# Modules_And_Sensors.net
KiCad netlist of a schematic drawn in Altium Designer
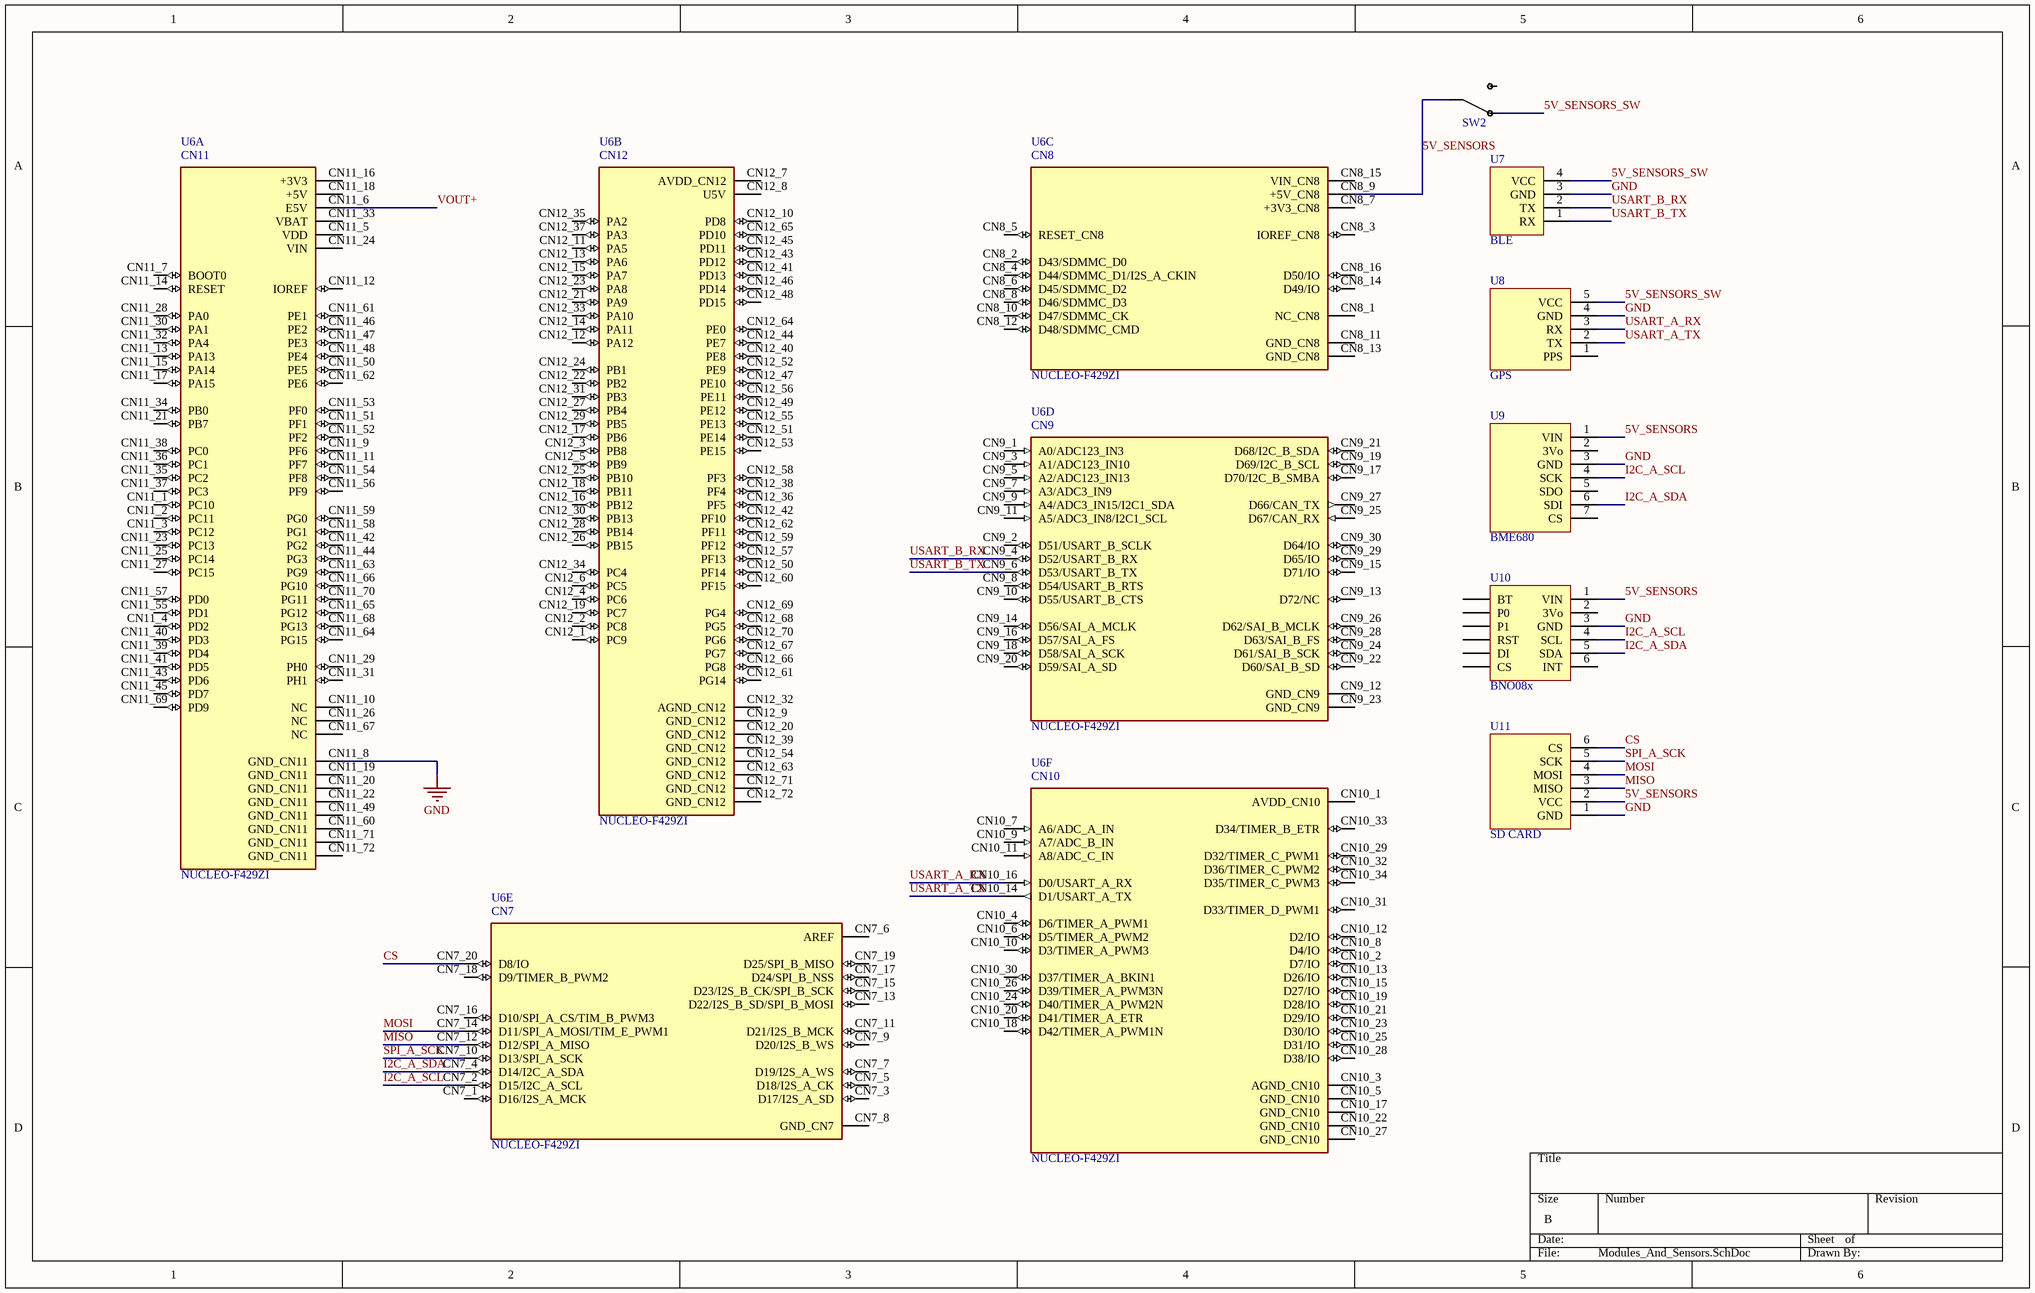
[diagram p0: Modules_And_Sensors.SchDoc]

(export (version "E")
  (design (tool "Eeschema 10.0.6"))
  (components
    (comp (ref "SW2") (value "SW") (footprint "SWITCH") (libsource (lib "Power_Schlib1") (part "Switch")))
    (comp (ref "U6")
      (value "NUCLEO-F429ZI")
      (footprint "MODULE_NUCLEO-F429ZI")
      (fields (field (name "MF") "STMicroelectronics"))
      (libsource (lib "NUCLEO-F429ZI") (part "NUCLEO-F429ZI"))
    )
    (comp (ref "U7") (value "BLE") (footprint "BLE") (libsource (lib "Power_Schlib1") (part "BLE")))
    (comp (ref "U8") (value "GPS") (footprint "GPS") (libsource (lib "Power_Schlib1") (part "GPS")))
    (comp (ref "U9") (value "BME680") (footprint "BME680") (libsource (lib "Power_Schlib1") (part "BME680")))
    (comp (ref "U10") (value "BNO08x") (footprint "BNO08x") (libsource (lib "Power_Schlib1") (part "BNO08x")))
    (comp (ref "U11")
      (value "SD CARD")
      (footprint "SD CARD")
      (libsource (lib "Power_Schlib1") (part "SD Card"))
    )
  )
  (nets
    (net (code "1") (name "/5V_SENSORS") (class "Default")
      (node (ref "SW2") (pin "2") (pinfunction "5_2") (pintype "passive"))
      (node (ref "U10") (pin "1") (pinfunction "VIN_1") (pintype "passive"))
      (node (ref "U11") (pin "2") (pinfunction "VCC_2") (pintype "passive"))
      (node (ref "U6") (pin "CN8_9") (pinfunction "+5V_CN8_CN8_9") (pintype "power_in"))
      (node (ref "U9") (pin "1") (pinfunction "VIN_1") (pintype "passive"))
    )
    (net (code "2") (name "/5V_SENSORS_SW") (class "Default")
      (node (ref "SW2") (pin "1") (pinfunction "7_1") (pintype "passive"))
      (node (ref "U7") (pin "4") (pinfunction "VCC_4") (pintype "passive"))
      (node (ref "U8") (pin "5") (pinfunction "VCC_5") (pintype "passive"))
    )
    (net (code "3") (name "/CS") (class "Default")
      (node (ref "U11") (pin "6") (pinfunction "CS_6") (pintype "passive"))
      (node (ref "U6") (pin "CN7_20") (pinfunction "D8/IO_CN7_20") (pintype "bidirectional"))
    )
    (net (code "4") (name "/I2C_A_SCL") (class "Default")
      (node (ref "U10") (pin "4") (pinfunction "SCL_4") (pintype "passive"))
      (node (ref "U6") (pin "CN7_2") (pinfunction "D15/I2C_A_SCL_CN7_2") (pintype "bidirectional"))
      (node (ref "U9") (pin "4") (pinfunction "SCK_4") (pintype "passive"))
    )
    (net (code "5") (name "/I2C_A_SDA") (class "Default")
      (node (ref "U10") (pin "5") (pinfunction "SDA_5") (pintype "passive"))
      (node (ref "U6") (pin "CN7_4") (pinfunction "D14/I2C_A_SDA_CN7_4") (pintype "bidirectional"))
      (node (ref "U9") (pin "6") (pinfunction "SDI_6") (pintype "passive"))
    )
    (net (code "6") (name "/MISO") (class "Default")
      (node (ref "U11") (pin "3") (pinfunction "MISO_3") (pintype "passive"))
      (node (ref "U6") (pin "CN7_12") (pinfunction "D12/SPI_A_MISO_CN7_12") (pintype "bidirectional"))
    )
    (net (code "7") (name "/MOSI") (class "Default")
      (node (ref "U11") (pin "4") (pinfunction "MOSI_4") (pintype "passive"))
      (node (ref "U6") (pin "CN7_14") (pinfunction "D11/SPI_A_MOSI/TIM_E_PWM1_CN7_14") (pintype "bidirectional"))
    )
    (net (code "8") (name "/SPI_A_SCK") (class "Default")
      (node (ref "U11") (pin "5") (pinfunction "SCK_5") (pintype "passive"))
      (node (ref "U6") (pin "CN7_10") (pinfunction "D13/SPI_A_SCK_CN7_10") (pintype "bidirectional"))
    )
    (net (code "9") (name "/USART_A_RX") (class "Default")
      (node (ref "U6") (pin "CN10_16") (pinfunction "D0/USART_A_RX_CN10_16") (pintype "input"))
      (node (ref "U8") (pin "3") (pinfunction "RX_3") (pintype "passive"))
    )
    (net (code "10") (name "/USART_A_TX") (class "Default")
      (node (ref "U6") (pin "CN10_14") (pinfunction "D1/USART_A_TX_CN10_14") (pintype "output"))
      (node (ref "U8") (pin "2") (pinfunction "TX_2") (pintype "passive"))
    )
    (net (code "11") (name "/USART_B_RX") (class "Default")
      (node (ref "U6") (pin "CN9_4") (pinfunction "D52/USART_B_RX_CN9_4") (pintype "bidirectional"))
      (node (ref "U7") (pin "2") (pinfunction "TX_2") (pintype "passive"))
    )
    (net (code "12") (name "/USART_B_TX") (class "Default")
      (node (ref "U6") (pin "CN9_6") (pinfunction "D53/USART_B_TX_CN9_6") (pintype "bidirectional"))
      (node (ref "U7") (pin "1") (pinfunction "RX_1") (pintype "passive"))
    )
    (net (code "13") (name "/VOUT+") (class "Default")
      (node (ref "U6") (pin "CN11_6") (pinfunction "E5V_CN11_6") (pintype "power_in"))
    )
    (net (code "14") (name "GND") (class "Default")
      (node (ref "U10") (pin "3") (pinfunction "GND_3") (pintype "passive"))
      (node (ref "U11") (pin "1") (pinfunction "GND_1") (pintype "passive"))
      (node (ref "U6") (pin "CN11_8") (pinfunction "GND_CN11_CN11_8") (pintype "power_in"))
      (node (ref "U7") (pin "3") (pinfunction "GND_3") (pintype "passive"))
      (node (ref "U8") (pin "4") (pinfunction "GND_4") (pintype "passive"))
      (node (ref "U9") (pin "3") (pinfunction "GND_3") (pintype "passive"))
    )
    (net (code "15") (name "unconnected-(SW2-6-Pad3)") (class "Default")
      (node (ref "SW2") (pin "3") (pinfunction "6_3") (pintype "passive"))
    )
    (net (code "16") (name "unconnected-(U6A-+3V3-PadCN11_16)") (class "Default")
      (node (ref "U6") (pin "CN11_16") (pinfunction "+3V3_CN11_16") (pintype "power_in"))
    )
    (net (code "17") (name "unconnected-(U6A-+5V-PadCN11_18)") (class "Default")
      (node (ref "U6") (pin "CN11_18") (pinfunction "+5V_CN11_18") (pintype "power_in"))
    )
    (net (code "18") (name "unconnected-(U6A-BOOT0-PadCN11_7)") (class "Default")
      (node (ref "U6") (pin "CN11_7") (pinfunction "BOOT0_CN11_7") (pintype "bidirectional"))
    )
    (net (code "19") (name "unconnected-(U6A-GND_CN11-PadCN11_19)") (class "Default")
      (node (ref "U6") (pin "CN11_19") (pinfunction "GND_CN11_CN11_19") (pintype "power_in"))
    )
    (net (code "20") (name "unconnected-(U6A-GND_CN11-PadCN11_20)") (class "Default")
      (node (ref "U6") (pin "CN11_20") (pinfunction "GND_CN11_CN11_20") (pintype "power_in"))
    )
    (net (code "21") (name "unconnected-(U6A-GND_CN11-PadCN11_22)") (class "Default")
      (node (ref "U6") (pin "CN11_22") (pinfunction "GND_CN11_CN11_22") (pintype "power_in"))
    )
    (net (code "22") (name "unconnected-(U6A-GND_CN11-PadCN11_49)") (class "Default")
      (node (ref "U6") (pin "CN11_49") (pinfunction "GND_CN11_CN11_49") (pintype "power_in"))
    )
    (net (code "23") (name "unconnected-(U6A-GND_CN11-PadCN11_60)") (class "Default")
      (node (ref "U6") (pin "CN11_60") (pinfunction "GND_CN11_CN11_60") (pintype "power_in"))
    )
    (net (code "24") (name "unconnected-(U6A-GND_CN11-PadCN11_71)") (class "Default")
      (node (ref "U6") (pin "CN11_71") (pinfunction "GND_CN11_CN11_71") (pintype "power_in"))
    )
    (net (code "25") (name "unconnected-(U6A-GND_CN11-PadCN11_72)") (class "Default")
      (node (ref "U6") (pin "CN11_72") (pinfunction "GND_CN11_CN11_72") (pintype "power_in"))
    )
    (net (code "26") (name "unconnected-(U6A-IOREF-PadCN11_12)") (class "Default")
      (node (ref "U6") (pin "CN11_12") (pinfunction "IOREF_CN11_12") (pintype "bidirectional"))
    )
    (net (code "27") (name "unconnected-(U6A-NC-PadCN11_10)") (class "Default")
      (node (ref "U6") (pin "CN11_10") (pinfunction "NC_CN11_10") (pintype "passive"))
    )
    (net (code "28") (name "unconnected-(U6A-NC-PadCN11_26)") (class "Default")
      (node (ref "U6") (pin "CN11_26") (pinfunction "NC_CN11_26") (pintype "passive"))
    )
    (net (code "29") (name "unconnected-(U6A-NC-PadCN11_67)") (class "Default")
      (node (ref "U6") (pin "CN11_67") (pinfunction "NC_CN11_67") (pintype "passive"))
    )
    (net (code "30") (name "unconnected-(U6A-PA0-PadCN11_28)") (class "Default")
      (node (ref "U6") (pin "CN11_28") (pinfunction "PA0_CN11_28") (pintype "bidirectional"))
    )
    (net (code "31") (name "unconnected-(U6A-PA1-PadCN11_30)") (class "Default")
      (node (ref "U6") (pin "CN11_30") (pinfunction "PA1_CN11_30") (pintype "bidirectional"))
    )
    (net (code "32") (name "unconnected-(U6A-PA4-PadCN11_32)") (class "Default")
      (node (ref "U6") (pin "CN11_32") (pinfunction "PA4_CN11_32") (pintype "bidirectional"))
    )
    (net (code "33") (name "unconnected-(U6A-PA13-PadCN11_13)") (class "Default")
      (node (ref "U6") (pin "CN11_13") (pinfunction "PA13_CN11_13") (pintype "bidirectional"))
    )
    (net (code "34") (name "unconnected-(U6A-PA14-PadCN11_15)") (class "Default")
      (node (ref "U6") (pin "CN11_15") (pinfunction "PA14_CN11_15") (pintype "bidirectional"))
    )
    (net (code "35") (name "unconnected-(U6A-PA15-PadCN11_17)") (class "Default")
      (node (ref "U6") (pin "CN11_17") (pinfunction "PA15_CN11_17") (pintype "bidirectional"))
    )
    (net (code "36") (name "unconnected-(U6A-PB0-PadCN11_34)") (class "Default")
      (node (ref "U6") (pin "CN11_34") (pinfunction "PB0_CN11_34") (pintype "bidirectional"))
    )
    (net (code "37") (name "unconnected-(U6A-PB7-PadCN11_21)") (class "Default")
      (node (ref "U6") (pin "CN11_21") (pinfunction "PB7_CN11_21") (pintype "bidirectional"))
    )
    (net (code "38") (name "unconnected-(U6A-PC0-PadCN11_38)") (class "Default")
      (node (ref "U6") (pin "CN11_38") (pinfunction "PC0_CN11_38") (pintype "bidirectional"))
    )
    (net (code "39") (name "unconnected-(U6A-PC1-PadCN11_36)") (class "Default")
      (node (ref "U6") (pin "CN11_36") (pinfunction "PC1_CN11_36") (pintype "bidirectional"))
    )
    (net (code "40") (name "unconnected-(U6A-PC2-PadCN11_35)") (class "Default")
      (node (ref "U6") (pin "CN11_35") (pinfunction "PC2_CN11_35") (pintype "bidirectional"))
    )
    (net (code "41") (name "unconnected-(U6A-PC3-PadCN11_37)") (class "Default")
      (node (ref "U6") (pin "CN11_37") (pinfunction "PC3_CN11_37") (pintype "bidirectional"))
    )
    (net (code "42") (name "unconnected-(U6A-PC10-PadCN11_1)") (class "Default")
      (node (ref "U6") (pin "CN11_1") (pinfunction "PC10_CN11_1") (pintype "bidirectional"))
    )
    (net (code "43") (name "unconnected-(U6A-PC11-PadCN11_2)") (class "Default")
      (node (ref "U6") (pin "CN11_2") (pinfunction "PC11_CN11_2") (pintype "bidirectional"))
    )
    (net (code "44") (name "unconnected-(U6A-PC12-PadCN11_3)") (class "Default")
      (node (ref "U6") (pin "CN11_3") (pinfunction "PC12_CN11_3") (pintype "bidirectional"))
    )
    (net (code "45") (name "unconnected-(U6A-PC13-PadCN11_23)") (class "Default")
      (node (ref "U6") (pin "CN11_23") (pinfunction "PC13_CN11_23") (pintype "bidirectional"))
    )
    (net (code "46") (name "unconnected-(U6A-PC14-PadCN11_25)") (class "Default")
      (node (ref "U6") (pin "CN11_25") (pinfunction "PC14_CN11_25") (pintype "bidirectional"))
    )
    (net (code "47") (name "unconnected-(U6A-PC15-PadCN11_27)") (class "Default")
      (node (ref "U6") (pin "CN11_27") (pinfunction "PC15_CN11_27") (pintype "bidirectional"))
    )
    (net (code "48") (name "unconnected-(U6A-PD0-PadCN11_57)") (class "Default")
      (node (ref "U6") (pin "CN11_57") (pinfunction "PD0_CN11_57") (pintype "bidirectional"))
    )
    (net (code "49") (name "unconnected-(U6A-PD1-PadCN11_55)") (class "Default")
      (node (ref "U6") (pin "CN11_55") (pinfunction "PD1_CN11_55") (pintype "bidirectional"))
    )
    (net (code "50") (name "unconnected-(U6A-PD2-PadCN11_4)") (class "Default")
      (node (ref "U6") (pin "CN11_4") (pinfunction "PD2_CN11_4") (pintype "bidirectional"))
    )
    (net (code "51") (name "unconnected-(U6A-PD3-PadCN11_40)") (class "Default")
      (node (ref "U6") (pin "CN11_40") (pinfunction "PD3_CN11_40") (pintype "bidirectional"))
    )
    (net (code "52") (name "unconnected-(U6A-PD4-PadCN11_39)") (class "Default")
      (node (ref "U6") (pin "CN11_39") (pinfunction "PD4_CN11_39") (pintype "bidirectional"))
    )
    (net (code "53") (name "unconnected-(U6A-PD5-PadCN11_41)") (class "Default")
      (node (ref "U6") (pin "CN11_41") (pinfunction "PD5_CN11_41") (pintype "bidirectional"))
    )
    (net (code "54") (name "unconnected-(U6A-PD6-PadCN11_43)") (class "Default")
      (node (ref "U6") (pin "CN11_43") (pinfunction "PD6_CN11_43") (pintype "bidirectional"))
    )
    (net (code "55") (name "unconnected-(U6A-PD7-PadCN11_45)") (class "Default")
      (node (ref "U6") (pin "CN11_45") (pinfunction "PD7_CN11_45") (pintype "bidirectional"))
    )
    (net (code "56") (name "unconnected-(U6A-PD9-PadCN11_69)") (class "Default")
      (node (ref "U6") (pin "CN11_69") (pinfunction "PD9_CN11_69") (pintype "bidirectional"))
    )
    (net (code "57") (name "unconnected-(U6A-PE1-PadCN11_61)") (class "Default")
      (node (ref "U6") (pin "CN11_61") (pinfunction "PE1_CN11_61") (pintype "bidirectional"))
    )
    (net (code "58") (name "unconnected-(U6A-PE2-PadCN11_46)") (class "Default")
      (node (ref "U6") (pin "CN11_46") (pinfunction "PE2_CN11_46") (pintype "bidirectional"))
    )
    (net (code "59") (name "unconnected-(U6A-PE3-PadCN11_47)") (class "Default")
      (node (ref "U6") (pin "CN11_47") (pinfunction "PE3_CN11_47") (pintype "bidirectional"))
    )
    (net (code "60") (name "unconnected-(U6A-PE4-PadCN11_48)") (class "Default")
      (node (ref "U6") (pin "CN11_48") (pinfunction "PE4_CN11_48") (pintype "bidirectional"))
    )
    (net (code "61") (name "unconnected-(U6A-PE5-PadCN11_50)") (class "Default")
      (node (ref "U6") (pin "CN11_50") (pinfunction "PE5_CN11_50") (pintype "bidirectional"))
    )
    (net (code "62") (name "unconnected-(U6A-PE6-PadCN11_62)") (class "Default")
      (node (ref "U6") (pin "CN11_62") (pinfunction "PE6_CN11_62") (pintype "bidirectional"))
    )
    (net (code "63") (name "unconnected-(U6A-PF0-PadCN11_53)") (class "Default")
      (node (ref "U6") (pin "CN11_53") (pinfunction "PF0_CN11_53") (pintype "bidirectional"))
    )
    (net (code "64") (name "unconnected-(U6A-PF1-PadCN11_51)") (class "Default")
      (node (ref "U6") (pin "CN11_51") (pinfunction "PF1_CN11_51") (pintype "bidirectional"))
    )
    (net (code "65") (name "unconnected-(U6A-PF2-PadCN11_52)") (class "Default")
      (node (ref "U6") (pin "CN11_52") (pinfunction "PF2_CN11_52") (pintype "bidirectional"))
    )
    (net (code "66") (name "unconnected-(U6A-PF6-PadCN11_9)") (class "Default")
      (node (ref "U6") (pin "CN11_9") (pinfunction "PF6_CN11_9") (pintype "bidirectional"))
    )
    (net (code "67") (name "unconnected-(U6A-PF7-PadCN11_11)") (class "Default")
      (node (ref "U6") (pin "CN11_11") (pinfunction "PF7_CN11_11") (pintype "bidirectional"))
    )
    (net (code "68") (name "unconnected-(U6A-PF8-PadCN11_54)") (class "Default")
      (node (ref "U6") (pin "CN11_54") (pinfunction "PF8_CN11_54") (pintype "bidirectional"))
    )
    (net (code "69") (name "unconnected-(U6A-PF9-PadCN11_56)") (class "Default")
      (node (ref "U6") (pin "CN11_56") (pinfunction "PF9_CN11_56") (pintype "bidirectional"))
    )
    (net (code "70") (name "unconnected-(U6A-PG0-PadCN11_59)") (class "Default")
      (node (ref "U6") (pin "CN11_59") (pinfunction "PG0_CN11_59") (pintype "bidirectional"))
    )
    (net (code "71") (name "unconnected-(U6A-PG1-PadCN11_58)") (class "Default")
      (node (ref "U6") (pin "CN11_58") (pinfunction "PG1_CN11_58") (pintype "bidirectional"))
    )
    (net (code "72") (name "unconnected-(U6A-PG2-PadCN11_42)") (class "Default")
      (node (ref "U6") (pin "CN11_42") (pinfunction "PG2_CN11_42") (pintype "bidirectional"))
    )
    (net (code "73") (name "unconnected-(U6A-PG3-PadCN11_44)") (class "Default")
      (node (ref "U6") (pin "CN11_44") (pinfunction "PG3_CN11_44") (pintype "bidirectional"))
    )
    (net (code "74") (name "unconnected-(U6A-PG9-PadCN11_63)") (class "Default")
      (node (ref "U6") (pin "CN11_63") (pinfunction "PG9_CN11_63") (pintype "bidirectional"))
    )
    (net (code "75") (name "unconnected-(U6A-PG10-PadCN11_66)") (class "Default")
      (node (ref "U6") (pin "CN11_66") (pinfunction "PG10_CN11_66") (pintype "bidirectional"))
    )
    (net (code "76") (name "unconnected-(U6A-PG11-PadCN11_70)") (class "Default")
      (node (ref "U6") (pin "CN11_70") (pinfunction "PG11_CN11_70") (pintype "bidirectional"))
    )
    (net (code "77") (name "unconnected-(U6A-PG12-PadCN11_65)") (class "Default")
      (node (ref "U6") (pin "CN11_65") (pinfunction "PG12_CN11_65") (pintype "bidirectional"))
    )
    (net (code "78") (name "unconnected-(U6A-PG13-PadCN11_68)") (class "Default")
      (node (ref "U6") (pin "CN11_68") (pinfunction "PG13_CN11_68") (pintype "bidirectional"))
    )
    (net (code "79") (name "unconnected-(U6A-PG15-PadCN11_64)") (class "Default")
      (node (ref "U6") (pin "CN11_64") (pinfunction "PG15_CN11_64") (pintype "bidirectional"))
    )
    (net (code "80") (name "unconnected-(U6A-PH0-PadCN11_29)") (class "Default")
      (node (ref "U6") (pin "CN11_29") (pinfunction "PH0_CN11_29") (pintype "bidirectional"))
    )
    (net (code "81") (name "unconnected-(U6A-PH1-PadCN11_31)") (class "Default")
      (node (ref "U6") (pin "CN11_31") (pinfunction "PH1_CN11_31") (pintype "bidirectional"))
    )
    (net (code "82") (name "unconnected-(U6A-RESET-PadCN11_14)") (class "Default")
      (node (ref "U6") (pin "CN11_14") (pinfunction "RESET_CN11_14") (pintype "bidirectional"))
    )
    (net (code "83") (name "unconnected-(U6A-VBAT-PadCN11_33)") (class "Default")
      (node (ref "U6") (pin "CN11_33") (pinfunction "VBAT_CN11_33") (pintype "power_in"))
    )
    (net (code "84") (name "unconnected-(U6A-VDD-PadCN11_5)") (class "Default")
      (node (ref "U6") (pin "CN11_5") (pinfunction "VDD_CN11_5") (pintype "power_in"))
    )
    (net (code "85") (name "unconnected-(U6A-VIN-PadCN11_24)") (class "Default")
      (node (ref "U6") (pin "CN11_24") (pinfunction "VIN_CN11_24") (pintype "power_in"))
    )
    (net (code "86") (name "unconnected-(U6B-AGND_CN12-PadCN12_32)") (class "Default")
      (node (ref "U6") (pin "CN12_32") (pinfunction "AGND_CN12_CN12_32") (pintype "power_in"))
    )
    (net (code "87") (name "unconnected-(U6B-AVDD_CN12-PadCN12_7)") (class "Default")
      (node (ref "U6") (pin "CN12_7") (pinfunction "AVDD_CN12_CN12_7") (pintype "power_in"))
    )
    (net (code "88") (name "unconnected-(U6B-GND_CN12-PadCN12_9)") (class "Default")
      (node (ref "U6") (pin "CN12_9") (pinfunction "GND_CN12_CN12_9") (pintype "power_in"))
    )
    (net (code "89") (name "unconnected-(U6B-GND_CN12-PadCN12_20)") (class "Default")
      (node (ref "U6") (pin "CN12_20") (pinfunction "GND_CN12_CN12_20") (pintype "power_in"))
    )
    (net (code "90") (name "unconnected-(U6B-GND_CN12-PadCN12_39)") (class "Default")
      (node (ref "U6") (pin "CN12_39") (pinfunction "GND_CN12_CN12_39") (pintype "power_in"))
    )
    (net (code "91") (name "unconnected-(U6B-GND_CN12-PadCN12_54)") (class "Default")
      (node (ref "U6") (pin "CN12_54") (pinfunction "GND_CN12_CN12_54") (pintype "power_in"))
    )
    (net (code "92") (name "unconnected-(U6B-GND_CN12-PadCN12_63)") (class "Default")
      (node (ref "U6") (pin "CN12_63") (pinfunction "GND_CN12_CN12_63") (pintype "power_in"))
    )
    (net (code "93") (name "unconnected-(U6B-GND_CN12-PadCN12_71)") (class "Default")
      (node (ref "U6") (pin "CN12_71") (pinfunction "GND_CN12_CN12_71") (pintype "power_in"))
    )
    (net (code "94") (name "unconnected-(U6B-GND_CN12-PadCN12_72)") (class "Default")
      (node (ref "U6") (pin "CN12_72") (pinfunction "GND_CN12_CN12_72") (pintype "power_in"))
    )
    (net (code "95") (name "unconnected-(U6B-PA2-PadCN12_35)") (class "Default")
      (node (ref "U6") (pin "CN12_35") (pinfunction "PA2_CN12_35") (pintype "bidirectional"))
    )
    (net (code "96") (name "unconnected-(U6B-PA3-PadCN12_37)") (class "Default")
      (node (ref "U6") (pin "CN12_37") (pinfunction "PA3_CN12_37") (pintype "bidirectional"))
    )
    (net (code "97") (name "unconnected-(U6B-PA5-PadCN12_11)") (class "Default")
      (node (ref "U6") (pin "CN12_11") (pinfunction "PA5_CN12_11") (pintype "bidirectional"))
    )
    (net (code "98") (name "unconnected-(U6B-PA6-PadCN12_13)") (class "Default")
      (node (ref "U6") (pin "CN12_13") (pinfunction "PA6_CN12_13") (pintype "bidirectional"))
    )
    (net (code "99") (name "unconnected-(U6B-PA7-PadCN12_15)") (class "Default")
      (node (ref "U6") (pin "CN12_15") (pinfunction "PA7_CN12_15") (pintype "bidirectional"))
    )
    (net (code "100") (name "unconnected-(U6B-PA8-PadCN12_23)") (class "Default")
      (node (ref "U6") (pin "CN12_23") (pinfunction "PA8_CN12_23") (pintype "bidirectional"))
    )
    (net (code "101") (name "unconnected-(U6B-PA9-PadCN12_21)") (class "Default")
      (node (ref "U6") (pin "CN12_21") (pinfunction "PA9_CN12_21") (pintype "bidirectional"))
    )
    (net (code "102") (name "unconnected-(U6B-PA10-PadCN12_33)") (class "Default")
      (node (ref "U6") (pin "CN12_33") (pinfunction "PA10_CN12_33") (pintype "bidirectional"))
    )
    (net (code "103") (name "unconnected-(U6B-PA11-PadCN12_14)") (class "Default")
      (node (ref "U6") (pin "CN12_14") (pinfunction "PA11_CN12_14") (pintype "bidirectional"))
    )
    (net (code "104") (name "unconnected-(U6B-PA12-PadCN12_12)") (class "Default")
      (node (ref "U6") (pin "CN12_12") (pinfunction "PA12_CN12_12") (pintype "bidirectional"))
    )
    (net (code "105") (name "unconnected-(U6B-PB1-PadCN12_24)") (class "Default")
      (node (ref "U6") (pin "CN12_24") (pinfunction "PB1_CN12_24") (pintype "bidirectional"))
    )
    (net (code "106") (name "unconnected-(U6B-PB2-PadCN12_22)") (class "Default")
      (node (ref "U6") (pin "CN12_22") (pinfunction "PB2_CN12_22") (pintype "bidirectional"))
    )
    (net (code "107") (name "unconnected-(U6B-PB3-PadCN12_31)") (class "Default")
      (node (ref "U6") (pin "CN12_31") (pinfunction "PB3_CN12_31") (pintype "bidirectional"))
    )
    (net (code "108") (name "unconnected-(U6B-PB4-PadCN12_27)") (class "Default")
      (node (ref "U6") (pin "CN12_27") (pinfunction "PB4_CN12_27") (pintype "bidirectional"))
    )
    (net (code "109") (name "unconnected-(U6B-PB5-PadCN12_29)") (class "Default")
      (node (ref "U6") (pin "CN12_29") (pinfunction "PB5_CN12_29") (pintype "bidirectional"))
    )
    (net (code "110") (name "unconnected-(U6B-PB6-PadCN12_17)") (class "Default")
      (node (ref "U6") (pin "CN12_17") (pinfunction "PB6_CN12_17") (pintype "bidirectional"))
    )
    (net (code "111") (name "unconnected-(U6B-PB8-PadCN12_3)") (class "Default")
      (node (ref "U6") (pin "CN12_3") (pinfunction "PB8_CN12_3") (pintype "bidirectional"))
    )
    (net (code "112") (name "unconnected-(U6B-PB9-PadCN12_5)") (class "Default")
      (node (ref "U6") (pin "CN12_5") (pinfunction "PB9_CN12_5") (pintype "bidirectional"))
    )
    (net (code "113") (name "unconnected-(U6B-PB10-PadCN12_25)") (class "Default")
      (node (ref "U6") (pin "CN12_25") (pinfunction "PB10_CN12_25") (pintype "bidirectional"))
    )
    (net (code "114") (name "unconnected-(U6B-PB11-PadCN12_18)") (class "Default")
      (node (ref "U6") (pin "CN12_18") (pinfunction "PB11_CN12_18") (pintype "bidirectional"))
    )
    (net (code "115") (name "unconnected-(U6B-PB12-PadCN12_16)") (class "Default")
      (node (ref "U6") (pin "CN12_16") (pinfunction "PB12_CN12_16") (pintype "bidirectional"))
    )
    (net (code "116") (name "unconnected-(U6B-PB13-PadCN12_30)") (class "Default")
      (node (ref "U6") (pin "CN12_30") (pinfunction "PB13_CN12_30") (pintype "bidirectional"))
    )
    (net (code "117") (name "unconnected-(U6B-PB14-PadCN12_28)") (class "Default")
      (node (ref "U6") (pin "CN12_28") (pinfunction "PB14_CN12_28") (pintype "bidirectional"))
    )
    (net (code "118") (name "unconnected-(U6B-PB15-PadCN12_26)") (class "Default")
      (node (ref "U6") (pin "CN12_26") (pinfunction "PB15_CN12_26") (pintype "bidirectional"))
    )
    (net (code "119") (name "unconnected-(U6B-PC4-PadCN12_34)") (class "Default")
      (node (ref "U6") (pin "CN12_34") (pinfunction "PC4_CN12_34") (pintype "bidirectional"))
    )
    (net (code "120") (name "unconnected-(U6B-PC5-PadCN12_6)") (class "Default")
      (node (ref "U6") (pin "CN12_6") (pinfunction "PC5_CN12_6") (pintype "bidirectional"))
    )
    (net (code "121") (name "unconnected-(U6B-PC6-PadCN12_4)") (class "Default")
      (node (ref "U6") (pin "CN12_4") (pinfunction "PC6_CN12_4") (pintype "bidirectional"))
    )
    (net (code "122") (name "unconnected-(U6B-PC7-PadCN12_19)") (class "Default")
      (node (ref "U6") (pin "CN12_19") (pinfunction "PC7_CN12_19") (pintype "bidirectional"))
    )
    (net (code "123") (name "unconnected-(U6B-PC8-PadCN12_2)") (class "Default")
      (node (ref "U6") (pin "CN12_2") (pinfunction "PC8_CN12_2") (pintype "bidirectional"))
    )
    (net (code "124") (name "unconnected-(U6B-PC9-PadCN12_1)") (class "Default")
      (node (ref "U6") (pin "CN12_1") (pinfunction "PC9_CN12_1") (pintype "bidirectional"))
    )
    (net (code "125") (name "unconnected-(U6B-PD8-PadCN12_10)") (class "Default")
      (node (ref "U6") (pin "CN12_10") (pinfunction "PD8_CN12_10") (pintype "bidirectional"))
    )
    (net (code "126") (name "unconnected-(U6B-PD10-PadCN12_65)") (class "Default")
      (node (ref "U6") (pin "CN12_65") (pinfunction "PD10_CN12_65") (pintype "bidirectional"))
    )
    (net (code "127") (name "unconnected-(U6B-PD11-PadCN12_45)") (class "Default")
      (node (ref "U6") (pin "CN12_45") (pinfunction "PD11_CN12_45") (pintype "bidirectional"))
    )
    (net (code "128") (name "unconnected-(U6B-PD12-PadCN12_43)") (class "Default")
      (node (ref "U6") (pin "CN12_43") (pinfunction "PD12_CN12_43") (pintype "bidirectional"))
    )
    (net (code "129") (name "unconnected-(U6B-PD13-PadCN12_41)") (class "Default")
      (node (ref "U6") (pin "CN12_41") (pinfunction "PD13_CN12_41") (pintype "bidirectional"))
    )
    (net (code "130") (name "unconnected-(U6B-PD14-PadCN12_46)") (class "Default")
      (node (ref "U6") (pin "CN12_46") (pinfunction "PD14_CN12_46") (pintype "bidirectional"))
    )
    (net (code "131") (name "unconnected-(U6B-PD15-PadCN12_48)") (class "Default")
      (node (ref "U6") (pin "CN12_48") (pinfunction "PD15_CN12_48") (pintype "bidirectional"))
    )
    (net (code "132") (name "unconnected-(U6B-PE0-PadCN12_64)") (class "Default")
      (node (ref "U6") (pin "CN12_64") (pinfunction "PE0_CN12_64") (pintype "bidirectional"))
    )
    (net (code "133") (name "unconnected-(U6B-PE7-PadCN12_44)") (class "Default")
      (node (ref "U6") (pin "CN12_44") (pinfunction "PE7_CN12_44") (pintype "bidirectional"))
    )
    (net (code "134") (name "unconnected-(U6B-PE8-PadCN12_40)") (class "Default")
      (node (ref "U6") (pin "CN12_40") (pinfunction "PE8_CN12_40") (pintype "bidirectional"))
    )
    (net (code "135") (name "unconnected-(U6B-PE9-PadCN12_52)") (class "Default")
      (node (ref "U6") (pin "CN12_52") (pinfunction "PE9_CN12_52") (pintype "bidirectional"))
    )
    (net (code "136") (name "unconnected-(U6B-PE10-PadCN12_47)") (class "Default")
      (node (ref "U6") (pin "CN12_47") (pinfunction "PE10_CN12_47") (pintype "bidirectional"))
    )
    (net (code "137") (name "unconnected-(U6B-PE11-PadCN12_56)") (class "Default")
      (node (ref "U6") (pin "CN12_56") (pinfunction "PE11_CN12_56") (pintype "bidirectional"))
    )
    (net (code "138") (name "unconnected-(U6B-PE12-PadCN12_49)") (class "Default")
      (node (ref "U6") (pin "CN12_49") (pinfunction "PE12_CN12_49") (pintype "bidirectional"))
    )
    (net (code "139") (name "unconnected-(U6B-PE13-PadCN12_55)") (class "Default")
      (node (ref "U6") (pin "CN12_55") (pinfunction "PE13_CN12_55") (pintype "bidirectional"))
    )
    (net (code "140") (name "unconnected-(U6B-PE14-PadCN12_51)") (class "Default")
      (node (ref "U6") (pin "CN12_51") (pinfunction "PE14_CN12_51") (pintype "bidirectional"))
    )
    (net (code "141") (name "unconnected-(U6B-PE15-PadCN12_53)") (class "Default")
      (node (ref "U6") (pin "CN12_53") (pinfunction "PE15_CN12_53") (pintype "bidirectional"))
    )
    (net (code "142") (name "unconnected-(U6B-PF3-PadCN12_58)") (class "Default")
      (node (ref "U6") (pin "CN12_58") (pinfunction "PF3_CN12_58") (pintype "bidirectional"))
    )
    (net (code "143") (name "unconnected-(U6B-PF4-PadCN12_38)") (class "Default")
      (node (ref "U6") (pin "CN12_38") (pinfunction "PF4_CN12_38") (pintype "bidirectional"))
    )
    (net (code "144") (name "unconnected-(U6B-PF5-PadCN12_36)") (class "Default")
      (node (ref "U6") (pin "CN12_36") (pinfunction "PF5_CN12_36") (pintype "bidirectional"))
    )
    (net (code "145") (name "unconnected-(U6B-PF10-PadCN12_42)") (class "Default")
      (node (ref "U6") (pin "CN12_42") (pinfunction "PF10_CN12_42") (pintype "bidirectional"))
    )
    (net (code "146") (name "unconnected-(U6B-PF11-PadCN12_62)") (class "Default")
      (node (ref "U6") (pin "CN12_62") (pinfunction "PF11_CN12_62") (pintype "bidirectional"))
    )
    (net (code "147") (name "unconnected-(U6B-PF12-PadCN12_59)") (class "Default")
      (node (ref "U6") (pin "CN12_59") (pinfunction "PF12_CN12_59") (pintype "bidirectional"))
    )
    (net (code "148") (name "unconnected-(U6B-PF13-PadCN12_57)") (class "Default")
      (node (ref "U6") (pin "CN12_57") (pinfunction "PF13_CN12_57") (pintype "bidirectional"))
    )
    (net (code "149") (name "unconnected-(U6B-PF14-PadCN12_50)") (class "Default")
      (node (ref "U6") (pin "CN12_50") (pinfunction "PF14_CN12_50") (pintype "bidirectional"))
    )
    (net (code "150") (name "unconnected-(U6B-PF15-PadCN12_60)") (class "Default")
      (node (ref "U6") (pin "CN12_60") (pinfunction "PF15_CN12_60") (pintype "bidirectional"))
    )
    (net (code "151") (name "unconnected-(U6B-PG4-PadCN12_69)") (class "Default")
      (node (ref "U6") (pin "CN12_69") (pinfunction "PG4_CN12_69") (pintype "bidirectional"))
    )
    (net (code "152") (name "unconnected-(U6B-PG5-PadCN12_68)") (class "Default")
      (node (ref "U6") (pin "CN12_68") (pinfunction "PG5_CN12_68") (pintype "bidirectional"))
    )
    (net (code "153") (name "unconnected-(U6B-PG6-PadCN12_70)") (class "Default")
      (node (ref "U6") (pin "CN12_70") (pinfunction "PG6_CN12_70") (pintype "bidirectional"))
    )
    (net (code "154") (name "unconnected-(U6B-PG7-PadCN12_67)") (class "Default")
      (node (ref "U6") (pin "CN12_67") (pinfunction "PG7_CN12_67") (pintype "bidirectional"))
    )
    (net (code "155") (name "unconnected-(U6B-PG8-PadCN12_66)") (class "Default")
      (node (ref "U6") (pin "CN12_66") (pinfunction "PG8_CN12_66") (pintype "bidirectional"))
    )
    (net (code "156") (name "unconnected-(U6B-PG14-PadCN12_61)") (class "Default")
      (node (ref "U6") (pin "CN12_61") (pinfunction "PG14_CN12_61") (pintype "bidirectional"))
    )
    (net (code "157") (name "unconnected-(U6B-U5V-PadCN12_8)") (class "Default")
      (node (ref "U6") (pin "CN12_8") (pinfunction "U5V_CN12_8") (pintype "power_in"))
    )
    (net (code "158") (name "unconnected-(U6C-+3V3_CN8-PadCN8_7)") (class "Default")
      (node (ref "U6") (pin "CN8_7") (pinfunction "+3V3_CN8_CN8_7") (pintype "power_in"))
    )
    (net (code "159") (name "unconnected-(U6C-D43{slash}SDMMC_D0-PadCN8_2)") (class "Default")
      (node (ref "U6") (pin "CN8_2") (pinfunction "D43/SDMMC_D0_CN8_2") (pintype "bidirectional"))
    )
    (net (code "160") (name "unconnected-(U6C-D44{slash}SDMMC_D1{slash}I2S_A_CKIN-PadCN8_4)") (class "Default")
      (node (ref "U6") (pin "CN8_4") (pinfunction "D44/SDMMC_D1/I2S_A_CKIN_CN8_4") (pintype "bidirectional"))
    )
    (net (code "161") (name "unconnected-(U6C-D45{slash}SDMMC_D2-PadCN8_6)") (class "Default")
      (node (ref "U6") (pin "CN8_6") (pinfunction "D45/SDMMC_D2_CN8_6") (pintype "bidirectional"))
    )
    (net (code "162") (name "unconnected-(U6C-D46{slash}SDMMC_D3-PadCN8_8)") (class "Default")
      (node (ref "U6") (pin "CN8_8") (pinfunction "D46/SDMMC_D3_CN8_8") (pintype "bidirectional"))
    )
    (net (code "163") (name "unconnected-(U6C-D47{slash}SDMMC_CK-PadCN8_10)") (class "Default")
      (node (ref "U6") (pin "CN8_10") (pinfunction "D47/SDMMC_CK_CN8_10") (pintype "bidirectional"))
    )
    (net (code "164") (name "unconnected-(U6C-D48{slash}SDMMC_CMD-PadCN8_12)") (class "Default")
      (node (ref "U6") (pin "CN8_12") (pinfunction "D48/SDMMC_CMD_CN8_12") (pintype "bidirectional"))
    )
    (net (code "165") (name "unconnected-(U6C-D49{slash}IO-PadCN8_14)") (class "Default")
      (node (ref "U6") (pin "CN8_14") (pinfunction "D49/IO_CN8_14") (pintype "bidirectional"))
    )
    (net (code "166") (name "unconnected-(U6C-D50{slash}IO-PadCN8_16)") (class "Default")
      (node (ref "U6") (pin "CN8_16") (pinfunction "D50/IO_CN8_16") (pintype "bidirectional"))
    )
    (net (code "167") (name "unconnected-(U6C-GND_CN8-PadCN8_11)") (class "Default")
      (node (ref "U6") (pin "CN8_11") (pinfunction "GND_CN8_CN8_11") (pintype "power_in"))
    )
    (net (code "168") (name "unconnected-(U6C-GND_CN8-PadCN8_13)") (class "Default")
      (node (ref "U6") (pin "CN8_13") (pinfunction "GND_CN8_CN8_13") (pintype "power_in"))
    )
    (net (code "169") (name "unconnected-(U6C-IOREF_CN8-PadCN8_3)") (class "Default")
      (node (ref "U6") (pin "CN8_3") (pinfunction "IOREF_CN8_CN8_3") (pintype "bidirectional"))
    )
    (net (code "170") (name "unconnected-(U6C-NC_CN8-PadCN8_1)") (class "Default")
      (node (ref "U6") (pin "CN8_1") (pinfunction "NC_CN8_CN8_1") (pintype "passive"))
    )
    (net (code "171") (name "unconnected-(U6C-RESET_CN8-PadCN8_5)") (class "Default")
      (node (ref "U6") (pin "CN8_5") (pinfunction "RESET_CN8_CN8_5") (pintype "bidirectional"))
    )
    (net (code "172") (name "unconnected-(U6C-VIN_CN8-PadCN8_15)") (class "Default")
      (node (ref "U6") (pin "CN8_15") (pinfunction "VIN_CN8_CN8_15") (pintype "power_in"))
    )
    (net (code "173") (name "unconnected-(U6D-A0{slash}ADC123_IN3-PadCN9_1)") (class "Default")
      (node (ref "U6") (pin "CN9_1") (pinfunction "A0/ADC123_IN3_CN9_1") (pintype "input"))
    )
    (net (code "174") (name "unconnected-(U6D-A1{slash}ADC123_IN10-PadCN9_3)") (class "Default")
      (node (ref "U6") (pin "CN9_3") (pinfunction "A1/ADC123_IN10_CN9_3") (pintype "input"))
    )
    (net (code "175") (name "unconnected-(U6D-A2{slash}ADC123_IN13-PadCN9_5)") (class "Default")
      (node (ref "U6") (pin "CN9_5") (pinfunction "A2/ADC123_IN13_CN9_5") (pintype "input"))
    )
    (net (code "176") (name "unconnected-(U6D-A3{slash}ADC3_IN9-PadCN9_7)") (class "Default")
      (node (ref "U6") (pin "CN9_7") (pinfunction "A3/ADC3_IN9_CN9_7") (pintype "input"))
    )
    (net (code "177") (name "unconnected-(U6D-A4{slash}ADC3_IN15{slash}I2C1_SDA-PadCN9_9)") (class "Default")
      (node (ref "U6") (pin "CN9_9") (pinfunction "A4/ADC3_IN15/I2C1_SDA_CN9_9") (pintype "input"))
    )
    (net (code "178") (name "unconnected-(U6D-A5{slash}ADC3_IN8{slash}I2C1_SCL-PadCN9_11)") (class "Default")
      (node (ref "U6") (pin "CN9_11") (pinfunction "A5/ADC3_IN8/I2C1_SCL_CN9_11") (pintype "input"))
    )
    (net (code "179") (name "unconnected-(U6D-D51{slash}USART_B_SCLK-PadCN9_2)") (class "Default")
      (node (ref "U6") (pin "CN9_2") (pinfunction "D51/USART_B_SCLK_CN9_2") (pintype "bidirectional"))
    )
    (net (code "180") (name "unconnected-(U6D-D54{slash}USART_B_RTS-PadCN9_8)") (class "Default")
      (node (ref "U6") (pin "CN9_8") (pinfunction "D54/USART_B_RTS_CN9_8") (pintype "bidirectional"))
    )
    (net (code "181") (name "unconnected-(U6D-D55{slash}USART_B_CTS-PadCN9_10)") (class "Default")
      (node (ref "U6") (pin "CN9_10") (pinfunction "D55/USART_B_CTS_CN9_10") (pintype "bidirectional"))
    )
    (net (code "182") (name "unconnected-(U6D-D56{slash}SAI_A_MCLK-PadCN9_14)") (class "Default")
      (node (ref "U6") (pin "CN9_14") (pinfunction "D56/SAI_A_MCLK_CN9_14") (pintype "bidirectional"))
    )
    (net (code "183") (name "unconnected-(U6D-D57{slash}SAI_A_FS-PadCN9_16)") (class "Default")
      (node (ref "U6") (pin "CN9_16") (pinfunction "D57/SAI_A_FS_CN9_16") (pintype "bidirectional"))
    )
    (net (code "184") (name "unconnected-(U6D-D58{slash}SAI_A_SCK-PadCN9_18)") (class "Default")
      (node (ref "U6") (pin "CN9_18") (pinfunction "D58/SAI_A_SCK_CN9_18") (pintype "bidirectional"))
    )
    (net (code "185") (name "unconnected-(U6D-D59{slash}SAI_A_SD-PadCN9_20)") (class "Default")
      (node (ref "U6") (pin "CN9_20") (pinfunction "D59/SAI_A_SD_CN9_20") (pintype "bidirectional"))
    )
    (net (code "186") (name "unconnected-(U6D-D60{slash}SAI_B_SD-PadCN9_22)") (class "Default")
      (node (ref "U6") (pin "CN9_22") (pinfunction "D60/SAI_B_SD_CN9_22") (pintype "bidirectional"))
    )
    (net (code "187") (name "unconnected-(U6D-D61{slash}SAI_B_SCK-PadCN9_24)") (class "Default")
      (node (ref "U6") (pin "CN9_24") (pinfunction "D61/SAI_B_SCK_CN9_24") (pintype "bidirectional"))
    )
    (net (code "188") (name "unconnected-(U6D-D62{slash}SAI_B_MCLK-PadCN9_26)") (class "Default")
      (node (ref "U6") (pin "CN9_26") (pinfunction "D62/SAI_B_MCLK_CN9_26") (pintype "bidirectional"))
    )
    (net (code "189") (name "unconnected-(U6D-D63{slash}SAI_B_FS-PadCN9_28)") (class "Default")
      (node (ref "U6") (pin "CN9_28") (pinfunction "D63/SAI_B_FS_CN9_28") (pintype "bidirectional"))
    )
    (net (code "190") (name "unconnected-(U6D-D64{slash}IO-PadCN9_30)") (class "Default")
      (node (ref "U6") (pin "CN9_30") (pinfunction "D64/IO_CN9_30") (pintype "bidirectional"))
    )
    (net (code "191") (name "unconnected-(U6D-D65{slash}IO-PadCN9_29)") (class "Default")
      (node (ref "U6") (pin "CN9_29") (pinfunction "D65/IO_CN9_29") (pintype "bidirectional"))
    )
    (net (code "192") (name "unconnected-(U6D-D66{slash}CAN_TX-PadCN9_27)") (class "Default")
      (node (ref "U6") (pin "CN9_27") (pinfunction "D66/CAN_TX_CN9_27") (pintype "output"))
    )
    (net (code "193") (name "unconnected-(U6D-D67{slash}CAN_RX-PadCN9_25)") (class "Default")
      (node (ref "U6") (pin "CN9_25") (pinfunction "D67/CAN_RX_CN9_25") (pintype "input"))
    )
    (net (code "194") (name "unconnected-(U6D-D68{slash}I2C_B_SDA-PadCN9_21)") (class "Default")
      (node (ref "U6") (pin "CN9_21") (pinfunction "D68/I2C_B_SDA_CN9_21") (pintype "bidirectional"))
    )
    (net (code "195") (name "unconnected-(U6D-D69{slash}I2C_B_SCL-PadCN9_19)") (class "Default")
      (node (ref "U6") (pin "CN9_19") (pinfunction "D69/I2C_B_SCL_CN9_19") (pintype "bidirectional"))
    )
    (net (code "196") (name "unconnected-(U6D-D70{slash}I2C_B_SMBA-PadCN9_17)") (class "Default")
      (node (ref "U6") (pin "CN9_17") (pinfunction "D70/I2C_B_SMBA_CN9_17") (pintype "bidirectional"))
    )
    (net (code "197") (name "unconnected-(U6D-D71{slash}IO-PadCN9_15)") (class "Default")
      (node (ref "U6") (pin "CN9_15") (pinfunction "D71/IO_CN9_15") (pintype "bidirectional"))
    )
    (net (code "198") (name "unconnected-(U6D-D72{slash}NC-PadCN9_13)") (class "Default")
      (node (ref "U6") (pin "CN9_13") (pinfunction "D72/NC_CN9_13") (pintype "bidirectional"))
    )
    (net (code "199") (name "unconnected-(U6D-GND_CN9-PadCN9_12)") (class "Default")
      (node (ref "U6") (pin "CN9_12") (pinfunction "GND_CN9_CN9_12") (pintype "power_in"))
    )
    (net (code "200") (name "unconnected-(U6D-GND_CN9-PadCN9_23)") (class "Default")
      (node (ref "U6") (pin "CN9_23") (pinfunction "GND_CN9_CN9_23") (pintype "power_in"))
    )
    (net (code "201") (name "unconnected-(U6E-AREF-PadCN7_6)") (class "Default")
      (node (ref "U6") (pin "CN7_6") (pinfunction "AREF_CN7_6") (pintype "power_in"))
    )
    (net (code "202") (name "unconnected-(U6E-D9{slash}TIMER_B_PWM2-PadCN7_18)") (class "Default")
      (node (ref "U6") (pin "CN7_18") (pinfunction "D9/TIMER_B_PWM2_CN7_18") (pintype "bidirectional"))
    )
    (net (code "203") (name "unconnected-(U6E-D10{slash}SPI_A_CS{slash}TIM_B_PWM3-PadCN7_16)") (class "Default")
      (node (ref "U6") (pin "CN7_16") (pinfunction "D10/SPI_A_CS/TIM_B_PWM3_CN7_16") (pintype "bidirectional"))
    )
    (net (code "204") (name "unconnected-(U6E-D16{slash}I2S_A_MCK-PadCN7_1)") (class "Default")
      (node (ref "U6") (pin "CN7_1") (pinfunction "D16/I2S_A_MCK_CN7_1") (pintype "bidirectional"))
    )
    (net (code "205") (name "unconnected-(U6E-D17{slash}I2S_A_SD-PadCN7_3)") (class "Default")
      (node (ref "U6") (pin "CN7_3") (pinfunction "D17/I2S_A_SD_CN7_3") (pintype "bidirectional"))
    )
    (net (code "206") (name "unconnected-(U6E-D18{slash}I2S_A_CK-PadCN7_5)") (class "Default")
      (node (ref "U6") (pin "CN7_5") (pinfunction "D18/I2S_A_CK_CN7_5") (pintype "bidirectional"))
    )
    (net (code "207") (name "unconnected-(U6E-D19{slash}I2S_A_WS-PadCN7_7)") (class "Default")
      (node (ref "U6") (pin "CN7_7") (pinfunction "D19/I2S_A_WS_CN7_7") (pintype "bidirectional"))
    )
    (net (code "208") (name "unconnected-(U6E-D20{slash}I2S_B_WS-PadCN7_9)") (class "Default")
      (node (ref "U6") (pin "CN7_9") (pinfunction "D20/I2S_B_WS_CN7_9") (pintype "bidirectional"))
    )
    (net (code "209") (name "unconnected-(U6E-D21{slash}I2S_B_MCK-PadCN7_11)") (class "Default")
      (node (ref "U6") (pin "CN7_11") (pinfunction "D21/I2S_B_MCK_CN7_11") (pintype "bidirectional"))
    )
    (net (code "210") (name "unconnected-(U6E-D22{slash}I2S_B_SD{slash}SPI_B_MOSI-PadCN7_13)") (class "Default")
      (node (ref "U6") (pin "CN7_13") (pinfunction "D22/I2S_B_SD/SPI_B_MOSI_CN7_13") (pintype "bidirectional"))
    )
    (net (code "211") (name "unconnected-(U6E-D23{slash}I2S_B_CK{slash}SPI_B_SCK-PadCN7_15)") (class "Default")
      (node (ref "U6") (pin "CN7_15") (pinfunction "D23/I2S_B_CK/SPI_B_SCK_CN7_15") (pintype "bidirectional"))
    )
    (net (code "212") (name "unconnected-(U6E-D24{slash}SPI_B_NSS-PadCN7_17)") (class "Default")
      (node (ref "U6") (pin "CN7_17") (pinfunction "D24/SPI_B_NSS_CN7_17") (pintype "bidirectional"))
    )
    (net (code "213") (name "unconnected-(U6E-D25{slash}SPI_B_MISO-PadCN7_19)") (class "Default")
      (node (ref "U6") (pin "CN7_19") (pinfunction "D25/SPI_B_MISO_CN7_19") (pintype "bidirectional"))
    )
    (net (code "214") (name "unconnected-(U6E-GND_CN7-PadCN7_8)") (class "Default")
      (node (ref "U6") (pin "CN7_8") (pinfunction "GND_CN7_CN7_8") (pintype "power_in"))
    )
    (net (code "215") (name "unconnected-(U6F-A6{slash}ADC_A_IN-PadCN10_7)") (class "Default")
      (node (ref "U6") (pin "CN10_7") (pinfunction "A6/ADC_A_IN_CN10_7") (pintype "input"))
    )
    (net (code "216") (name "unconnected-(U6F-A7{slash}ADC_B_IN-PadCN10_9)") (class "Default")
      (node (ref "U6") (pin "CN10_9") (pinfunction "A7/ADC_B_IN_CN10_9") (pintype "input"))
    )
    (net (code "217") (name "unconnected-(U6F-A8{slash}ADC_C_IN-PadCN10_11)") (class "Default")
      (node (ref "U6") (pin "CN10_11") (pinfunction "A8/ADC_C_IN_CN10_11") (pintype "input"))
    )
    (net (code "218") (name "unconnected-(U6F-AGND_CN10-PadCN10_3)") (class "Default")
      (node (ref "U6") (pin "CN10_3") (pinfunction "AGND_CN10_CN10_3") (pintype "power_in"))
    )
    (net (code "219") (name "unconnected-(U6F-AVDD_CN10-PadCN10_1)") (class "Default")
      (node (ref "U6") (pin "CN10_1") (pinfunction "AVDD_CN10_CN10_1") (pintype "power_in"))
    )
    (net (code "220") (name "unconnected-(U6F-D2{slash}IO-PadCN10_12)") (class "Default")
      (node (ref "U6") (pin "CN10_12") (pinfunction "D2/IO_CN10_12") (pintype "bidirectional"))
    )
    (net (code "221") (name "unconnected-(U6F-D3{slash}TIMER_A_PWM3-PadCN10_10)") (class "Default")
      (node (ref "U6") (pin "CN10_10") (pinfunction "D3/TIMER_A_PWM3_CN10_10") (pintype "bidirectional"))
    )
    (net (code "222") (name "unconnected-(U6F-D4{slash}IO-PadCN10_8)") (class "Default")
      (node (ref "U6") (pin "CN10_8") (pinfunction "D4/IO_CN10_8") (pintype "bidirectional"))
    )
    (net (code "223") (name "unconnected-(U6F-D5{slash}TIMER_A_PWM2-PadCN10_6)") (class "Default")
      (node (ref "U6") (pin "CN10_6") (pinfunction "D5/TIMER_A_PWM2_CN10_6") (pintype "bidirectional"))
    )
    (net (code "224") (name "unconnected-(U6F-D6{slash}TIMER_A_PWM1-PadCN10_4)") (class "Default")
      (node (ref "U6") (pin "CN10_4") (pinfunction "D6/TIMER_A_PWM1_CN10_4") (pintype "bidirectional"))
    )
    (net (code "225") (name "unconnected-(U6F-D7{slash}IO-PadCN10_2)") (class "Default")
      (node (ref "U6") (pin "CN10_2") (pinfunction "D7/IO_CN10_2") (pintype "bidirectional"))
    )
    (net (code "226") (name "unconnected-(U6F-D26{slash}IO-PadCN10_13)") (class "Default")
      (node (ref "U6") (pin "CN10_13") (pinfunction "D26/IO_CN10_13") (pintype "bidirectional"))
    )
    (net (code "227") (name "unconnected-(U6F-D27{slash}IO-PadCN10_15)") (class "Default")
      (node (ref "U6") (pin "CN10_15") (pinfunction "D27/IO_CN10_15") (pintype "bidirectional"))
    )
    (net (code "228") (name "unconnected-(U6F-D28{slash}IO-PadCN10_19)") (class "Default")
      (node (ref "U6") (pin "CN10_19") (pinfunction "D28/IO_CN10_19") (pintype "bidirectional"))
    )
    (net (code "229") (name "unconnected-(U6F-D29{slash}IO-PadCN10_21)") (class "Default")
      (node (ref "U6") (pin "CN10_21") (pinfunction "D29/IO_CN10_21") (pintype "bidirectional"))
    )
    (net (code "230") (name "unconnected-(U6F-D30{slash}IO-PadCN10_23)") (class "Default")
      (node (ref "U6") (pin "CN10_23") (pinfunction "D30/IO_CN10_23") (pintype "bidirectional"))
    )
    (net (code "231") (name "unconnected-(U6F-D31{slash}IO-PadCN10_25)") (class "Default")
      (node (ref "U6") (pin "CN10_25") (pinfunction "D31/IO_CN10_25") (pintype "bidirectional"))
    )
    (net (code "232") (name "unconnected-(U6F-D32{slash}TIMER_C_PWM1-PadCN10_29)") (class "Default")
      (node (ref "U6") (pin "CN10_29") (pinfunction "D32/TIMER_C_PWM1_CN10_29") (pintype "bidirectional"))
    )
    (net (code "233") (name "unconnected-(U6F-D33{slash}TIMER_D_PWM1-PadCN10_31)") (class "Default")
      (node (ref "U6") (pin "CN10_31") (pinfunction "D33/TIMER_D_PWM1_CN10_31") (pintype "bidirectional"))
    )
    (net (code "234") (name "unconnected-(U6F-D34{slash}TIMER_B_ETR-PadCN10_33)") (class "Default")
      (node (ref "U6") (pin "CN10_33") (pinfunction "D34/TIMER_B_ETR_CN10_33") (pintype "bidirectional"))
    )
    (net (code "235") (name "unconnected-(U6F-D35{slash}TIMER_C_PWM3-PadCN10_34)") (class "Default")
      (node (ref "U6") (pin "CN10_34") (pinfunction "D35/TIMER_C_PWM3_CN10_34") (pintype "bidirectional"))
    )
    (net (code "236") (name "unconnected-(U6F-D36{slash}TIMER_C_PWM2-PadCN10_32)") (class "Default")
      (node (ref "U6") (pin "CN10_32") (pinfunction "D36/TIMER_C_PWM2_CN10_32") (pintype "bidirectional"))
    )
    (net (code "237") (name "unconnected-(U6F-D37{slash}TIMER_A_BKIN1-PadCN10_30)") (class "Default")
      (node (ref "U6") (pin "CN10_30") (pinfunction "D37/TIMER_A_BKIN1_CN10_30") (pintype "bidirectional"))
    )
    (net (code "238") (name "unconnected-(U6F-D38{slash}IO-PadCN10_28)") (class "Default")
      (node (ref "U6") (pin "CN10_28") (pinfunction "D38/IO_CN10_28") (pintype "bidirectional"))
    )
    (net (code "239") (name "unconnected-(U6F-D39{slash}TIMER_A_PWM3N-PadCN10_26)") (class "Default")
      (node (ref "U6") (pin "CN10_26") (pinfunction "D39/TIMER_A_PWM3N_CN10_26") (pintype "bidirectional"))
    )
    (net (code "240") (name "unconnected-(U6F-D40{slash}TIMER_A_PWM2N-PadCN10_24)") (class "Default")
      (node (ref "U6") (pin "CN10_24") (pinfunction "D40/TIMER_A_PWM2N_CN10_24") (pintype "bidirectional"))
    )
    (net (code "241") (name "unconnected-(U6F-D41{slash}TIMER_A_ETR-PadCN10_20)") (class "Default")
      (node (ref "U6") (pin "CN10_20") (pinfunction "D41/TIMER_A_ETR_CN10_20") (pintype "bidirectional"))
    )
    (net (code "242") (name "unconnected-(U6F-D42{slash}TIMER_A_PWM1N-PadCN10_18)") (class "Default")
      (node (ref "U6") (pin "CN10_18") (pinfunction "D42/TIMER_A_PWM1N_CN10_18") (pintype "bidirectional"))
    )
    (net (code "243") (name "unconnected-(U6F-GND_CN10-PadCN10_5)") (class "Default")
      (node (ref "U6") (pin "CN10_5") (pinfunction "GND_CN10_CN10_5") (pintype "power_in"))
    )
    (net (code "244") (name "unconnected-(U6F-GND_CN10-PadCN10_17)") (class "Default")
      (node (ref "U6") (pin "CN10_17") (pinfunction "GND_CN10_CN10_17") (pintype "power_in"))
    )
    (net (code "245") (name "unconnected-(U6F-GND_CN10-PadCN10_22)") (class "Default")
      (node (ref "U6") (pin "CN10_22") (pinfunction "GND_CN10_CN10_22") (pintype "power_in"))
    )
    (net (code "246") (name "unconnected-(U6F-GND_CN10-PadCN10_27)") (class "Default")
      (node (ref "U6") (pin "CN10_27") (pinfunction "GND_CN10_CN10_27") (pintype "power_in"))
    )
    (net (code "247") (name "unconnected-(U8-PPS-Pad1)") (class "Default")
      (node (ref "U8") (pin "1") (pinfunction "PPS_1") (pintype "passive"))
    )
    (net (code "248") (name "unconnected-(U9-3Vo-Pad2)") (class "Default")
      (node (ref "U9") (pin "2") (pinfunction "3Vo_2") (pintype "passive"))
    )
    (net (code "249") (name "unconnected-(U9-CS-Pad7)") (class "Default")
      (node (ref "U9") (pin "7") (pinfunction "CS_7") (pintype "passive"))
    )
    (net (code "250") (name "unconnected-(U9-SDO-Pad5)") (class "Default")
      (node (ref "U9") (pin "5") (pinfunction "SDO_5") (pintype "passive"))
    )
    (net (code "251") (name "unconnected-(U10-3Vo-Pad2)") (class "Default")
      (node (ref "U10") (pin "2") (pinfunction "3Vo_2") (pintype "passive"))
    )
    (net (code "252") (name "unconnected-(U10-BT-Pad)") (class "Default")
      (node (ref "U10") (pin "") (pinfunction "BT_") (pintype "passive"))
    )
    (net (code "253") (name "unconnected-(U10-CS-Pad)") (class "Default")
      (node (ref "U10") (pin "") (pinfunction "CS_") (pintype "passive"))
    )
    (net (code "254") (name "unconnected-(U10-DI-Pad)") (class "Default")
      (node (ref "U10") (pin "") (pinfunction "DI_") (pintype "passive"))
    )
    (net (code "255") (name "unconnected-(U10-INT-Pad6)") (class "Default")
      (node (ref "U10") (pin "6") (pinfunction "INT_6") (pintype "passive"))
    )
    (net (code "256") (name "unconnected-(U10-P0-Pad)") (class "Default")
      (node (ref "U10") (pin "") (pinfunction "P0_") (pintype "passive"))
    )
    (net (code "257") (name "unconnected-(U10-P1-Pad)") (class "Default")
      (node (ref "U10") (pin "") (pinfunction "P1_") (pintype "passive"))
    )
    (net (code "258") (name "unconnected-(U10-RST-Pad)") (class "Default")
      (node (ref "U10") (pin "") (pinfunction "RST_") (pintype "passive"))
    )
  )
)
